# UART_Control.net
KiCad netlist of a schematic drawn in Altium Designer
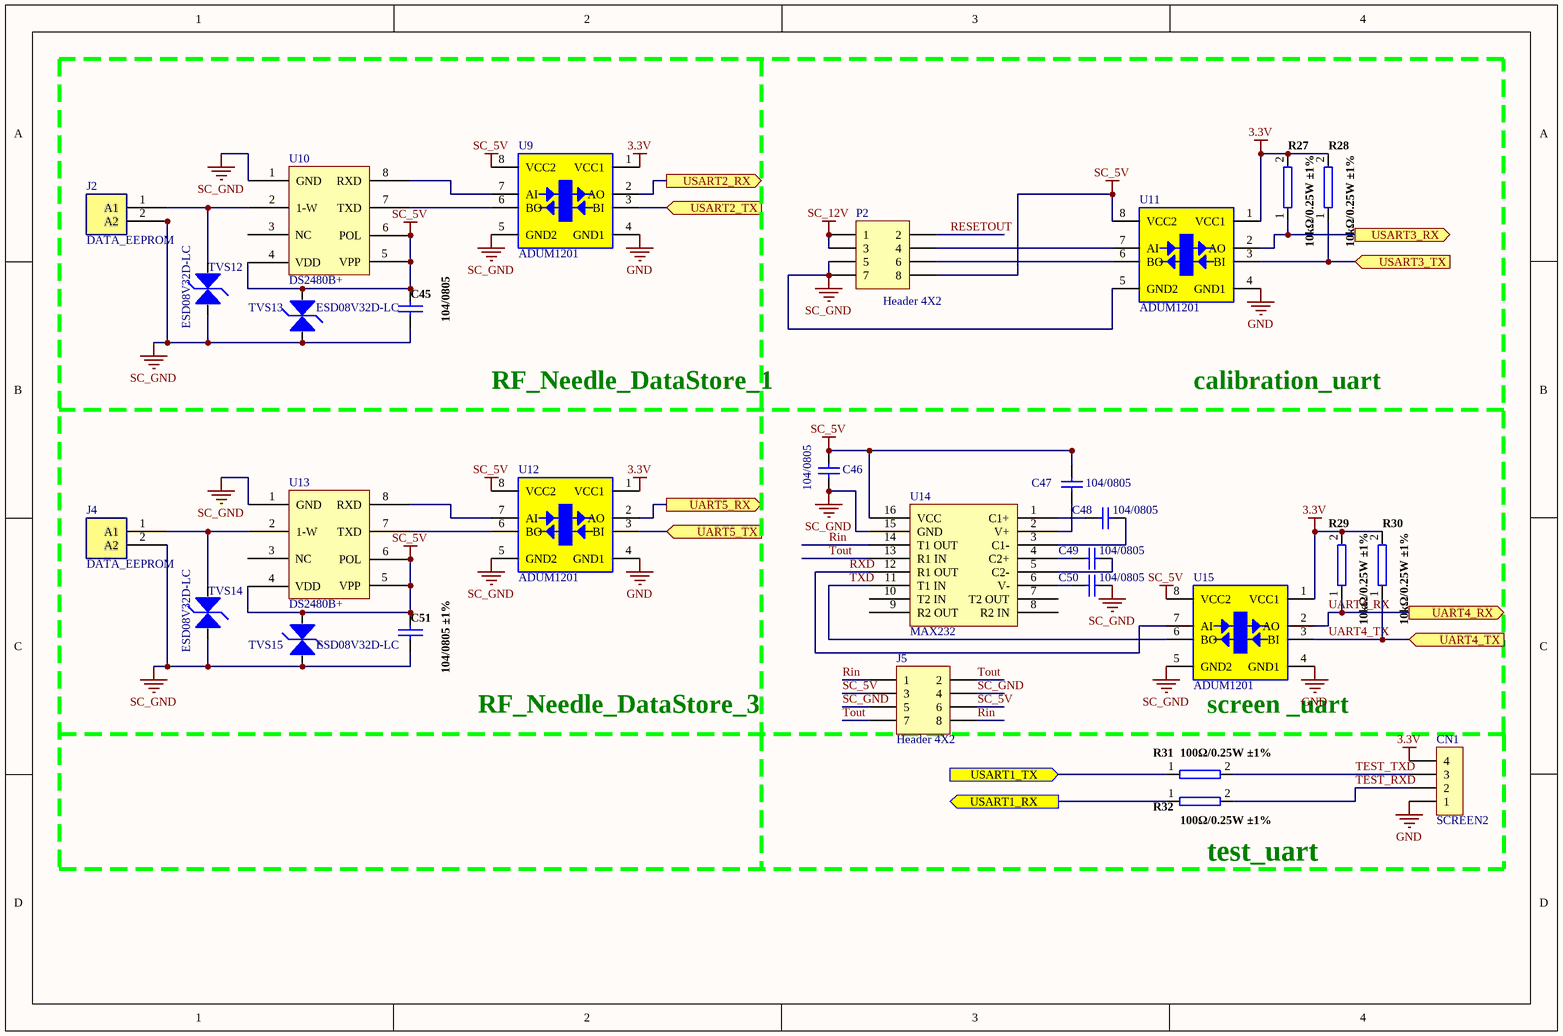
[diagram p0: UART_Control.SchDoc]

(export (version "E")
  (design (tool "Eeschema 10.0.6"))
  (components
    (comp (ref "C45")
      (value "104/0805")
      (footprint "C0805")
      (description "贴片电容 104/25V ±1% C0805")
      (libsource (lib "COOLCONTROL") (part "CAP"))
    )
    (comp (ref "C46")
      (value "104/0805")
      (footprint "C0805")
      (description "贴片电容 104/25V ±1% C0805")
      (fields (field (name "PUBLISHER") "Altium Limited"))
      (libsource (lib "Miscellaneous Devices") (part "Cap"))
    )
    (comp (ref "C47")
      (value "104/0805")
      (footprint "C0805")
      (description "贴片电容 104/25V ±1% C0805")
      (fields (field (name "PUBLISHER") "Altium Limited"))
      (libsource (lib "") (part "Cap_1"))
    )
    (comp (ref "C48")
      (value "104/0805")
      (footprint "C0805")
      (description "贴片电容 104/25V ±1% C0805")
      (fields (field (name "PUBLISHER") "Altium Limited"))
      (libsource (lib "") (part "Cap_1"))
    )
    (comp (ref "C49")
      (value "104/0805")
      (footprint "C0805")
      (description "贴片电容 104/25V ±1% C0805")
      (fields (field (name "PUBLISHER") "Altium Limited"))
      (libsource (lib "") (part "Cap_1"))
    )
    (comp (ref "C50")
      (value "104/0805")
      (footprint "C0805")
      (description "贴片电容 104/25V ±1% C0805")
      (fields (field (name "PUBLISHER") "Altium Limited"))
      (libsource (lib "") (part "Cap_1"))
    )
    (comp (ref "C51")
      (value "104/0805 ±1%")
      (footprint "C0805")
      (description "贴片电容 104/25V ±1% C0805")
      (libsource (lib "COOLCONTROL") (part "CAP"))
    )
    (comp (ref "CN1")
      (value "SCREEN2")
      (footprint "COOLCONTROL:4Pin-2.54")
      (description "单排排针（4针） 2.54mm 4Pin-2.54")
      (libsource (lib "COOLCONTROL") (part "CON4"))
    )
    (comp (ref "J2")
      (value "DATA_EEPROM")
      (footprint "COOLCONTROL:XH2")
      (description "插座式端子 XH2.54-2P 250V(DC/AC) 3A")
      (libsource (lib "COOLCONTROL") (part "CON2"))
    )
    (comp (ref "J4")
      (value "DATA_EEPROM")
      (footprint "XH2")
      (description "插座式端子 XH2.54-2P 250V(DC/AC) 3A")
      (libsource (lib "COOLCONTROL") (part "CON2"))
    )
    (comp (ref "J5")
      (value "Header 4X2")
      (footprint "IDC4*2")
      (description "双排排针（4针） 2.54mm IDC4*2")
      (fields (field (name "PUBLISHER") "Altium Limited"))
      (libsource (lib "Miscellaneous Connectors") (part "Header 4X2"))
    )
    (comp (ref "P2")
      (value "Header 4X2")
      (footprint "pcb2D3D库0903:RJ45")
      (description "RJ45插座 RJ45")
      (fields (field (name "PUBLISHER") "Altium Limited"))
      (libsource (lib "Miscellaneous Connectors") (part "Header 4X2"))
    )
    (comp (ref "R27")
      (value "10kΩ/0.25W ±1%")
      (footprint "R0805")
      (description "贴片电阻 10kΩ 0.25W ±1% R0805")
      (libsource (lib "*") (part "RES2"))
    )
    (comp (ref "R28")
      (value "10kΩ/0.25W ±1%")
      (footprint "R0805")
      (description "贴片电阻 10kΩ 0.25W ±1% R0805")
      (libsource (lib "*") (part "RES2"))
    )
    (comp (ref "R29")
      (value "10kΩ/0.25W ±1%")
      (footprint "R0805")
      (description "贴片电阻 10kΩ 0.25W ±1% R0805")
      (libsource (lib "*") (part "RES2"))
    )
    (comp (ref "R30")
      (value "10kΩ/0.25W ±1%")
      (footprint "R0805")
      (description "贴片电阻 10kΩ 0.25W ±1% R0805")
      (libsource (lib "*") (part "RES2"))
    )
    (comp (ref "R31")
      (value "100Ω/0.25W ±1%")
      (footprint "COOLCONTROL:R0805")
      (description "贴片电阻 100Ω 0.25W ±1% R0805")
      (libsource (lib "*") (part "RES2"))
    )
    (comp (ref "R32")
      (value "100Ω/0.25W ±1%")
      (footprint "COOLCONTROL:R0805")
      (description "贴片电阻 100Ω 0.25W ±1% R0805")
      (libsource (lib "*") (part "RES2"))
    )
    (comp (ref "TVS12")
      (value "ESD08V32D-LC")
      (footprint "SOD323")
      (description "ESD静电二极管 ESD08V32D-LC 5V 15KV 40A SOD323")
      (libsource (lib "COOLCONTROL") (part "TVS"))
    )
    (comp (ref "TVS13")
      (value "ESD08V32D-LC")
      (footprint "SOD323")
      (description "ESD静电二极管 ESD08V32D-LC 5V 15KV 40A SOD323")
      (libsource (lib "COOLCONTROL") (part "TVS"))
    )
    (comp (ref "TVS14")
      (value "ESD08V32D-LC")
      (footprint "SOD323")
      (description "ESD静电二极管 ESD08V32D-LC 5V 15KV 40A SOD323")
      (libsource (lib "COOLCONTROL") (part "TVS"))
    )
    (comp (ref "TVS15")
      (value "ESD08V32D-LC")
      (footprint "SOD323")
      (description "ESD静电二极管 ESD08V32D-LC 5V 15KV 40A SOD323")
      (libsource (lib "COOLCONTROL") (part "TVS"))
    )
    (comp (ref "U9")
      (value "ADUM1201")
      (footprint "SOIC8_N")
      (description "双通道数字隔离器 ADUM1201 SOIC8_N")
      (libsource (lib "COOLCONTROL") (part "ADUM1201"))
    )
    (comp (ref "U10")
      (value "DS2480B+")
      (footprint "SOIC8_N")
      (description "1-Wire线驱动器 DS2480B SOIC8_N")
      (libsource (lib "COOLCONTROL") (part "DS2480B+"))
    )
    (comp (ref "U11")
      (value "ADUM1201")
      (footprint "SOIC8_N")
      (description "双通道数字隔离器 ADUM1201 SOIC8_N")
      (libsource (lib "COOLCONTROL") (part "ADUM1201"))
    )
    (comp (ref "U12")
      (value "ADUM1201")
      (footprint "SOIC8_N")
      (description "双通道数字隔离器 ADUM1201 SOIC8_N")
      (libsource (lib "COOLCONTROL") (part "ADUM1201"))
    )
    (comp (ref "U13")
      (value "DS2480B+")
      (footprint "SOIC8_N")
      (description "1-Wire线驱动器 DS2480B SOIC8_N")
      (libsource (lib "COOLCONTROL") (part "DS2480B+"))
    )
    (comp (ref "U14")
      (value "MAX232")
      (footprint "SOP16")
      (description "串口通信转换芯片 MAX232 SOP16")
      (libsource (lib "miniCoreBoard") (part "MAX232_DIP16"))
    )
    (comp (ref "U15")
      (value "ADUM1201")
      (footprint "SOIC8_N")
      (description "双通道数字隔离器 ADUM1201 SOIC8_N")
      (libsource (lib "COOLCONTROL") (part "ADUM1201"))
    )
  )
  (nets
    (net (code "1") (name "/RESETOUT") (class "Default")
      (node (ref "P2") (pin "2") (pinfunction "2_2") (pintype "passive"))
    )
    (net (code "2") (name "/RXD") (class "Default")
      (node (ref "U14") (pin "12") (pinfunction "R1_OUT_12") (pintype "passive"))
      (node (ref "U15") (pin "7") (pinfunction "AI_7") (pintype "passive"))
    )
    (net (code "3") (name "/Rin") (class "Default")
      (node (ref "J5") (pin "1") (pinfunction "1_1") (pintype "passive"))
      (node (ref "J5") (pin "8") (pinfunction "8_8") (pintype "passive"))
      (node (ref "U14") (pin "14") (pinfunction "T1_OUT_14") (pintype "passive"))
    )
    (net (code "4") (name "/TEST_RXD") (class "Default")
      (node (ref "CN1") (pin "2") (pinfunction "2_2") (pintype "passive"))
      (node (ref "R32") (pin "2") (pintype "passive"))
    )
    (net (code "5") (name "/TEST_TXD") (class "Default")
      (node (ref "CN1") (pin "3") (pinfunction "3_3") (pintype "passive"))
      (node (ref "R31") (pin "2") (pintype "passive"))
    )
    (net (code "6") (name "/TXD") (class "Default")
      (node (ref "U14") (pin "11") (pinfunction "T1_IN_11") (pintype "passive"))
      (node (ref "U15") (pin "6") (pinfunction "BO_6") (pintype "passive"))
    )
    (net (code "7") (name "/Tout") (class "Default")
      (node (ref "J5") (pin "2") (pinfunction "2_2") (pintype "passive"))
      (node (ref "J5") (pin "7") (pinfunction "7_7") (pintype "passive"))
      (node (ref "U14") (pin "13") (pinfunction "R1_IN_13") (pintype "passive"))
    )
    (net (code "8") (name "/UART4_RX") (class "Default")
      (node (ref "R29") (pin "1") (pintype "passive"))
      (node (ref "U15") (pin "2") (pinfunction "AO_2") (pintype "passive"))
    )
    (net (code "9") (name "/UART4_TX") (class "Default")
      (node (ref "R30") (pin "1") (pintype "passive"))
      (node (ref "U15") (pin "3") (pinfunction "BI_3") (pintype "passive"))
    )
    (net (code "10") (name "/UART5_RX") (class "Default")
      (node (ref "U12") (pin "2") (pinfunction "AO_2") (pintype "passive"))
    )
    (net (code "11") (name "/UART5_TX") (class "Default")
      (node (ref "U12") (pin "3") (pinfunction "BI_3") (pintype "passive"))
    )
    (net (code "12") (name "/USART1_RX") (class "Default") (node (ref "R32") (pin "1") (pintype "passive")))
    (net (code "13") (name "/USART1_TX") (class "Default") (node (ref "R31") (pin "1") (pintype "passive")))
    (net (code "14") (name "/USART2_RX") (class "Default")
      (node (ref "U9") (pin "2") (pinfunction "AO_2") (pintype "passive"))
    )
    (net (code "15") (name "/USART2_TX") (class "Default")
      (node (ref "U9") (pin "3") (pinfunction "BI_3") (pintype "passive"))
    )
    (net (code "16") (name "/USART3_RX") (class "Default")
      (node (ref "R27") (pin "1") (pintype "passive"))
      (node (ref "U11") (pin "2") (pinfunction "AO_2") (pintype "passive"))
    )
    (net (code "17") (name "/USART3_TX") (class "Default")
      (node (ref "R28") (pin "1") (pintype "passive"))
      (node (ref "U11") (pin "3") (pinfunction "BI_3") (pintype "passive"))
    )
    (net (code "18") (name "3.3V") (class "Default")
      (node (ref "CN1") (pin "4") (pinfunction "4_4") (pintype "passive"))
      (node (ref "R27") (pin "2") (pintype "passive"))
      (node (ref "R28") (pin "2") (pintype "passive"))
      (node (ref "R29") (pin "2") (pintype "passive"))
      (node (ref "R30") (pin "2") (pintype "passive"))
      (node (ref "U11") (pin "1") (pinfunction "VCC1_1") (pintype "passive"))
      (node (ref "U12") (pin "1") (pinfunction "VCC1_1") (pintype "passive"))
      (node (ref "U15") (pin "1") (pinfunction "VCC1_1") (pintype "passive"))
      (node (ref "U9") (pin "1") (pinfunction "VCC1_1") (pintype "passive"))
    )
    (net (code "19") (name "GND") (class "Default")
      (node (ref "CN1") (pin "1") (pinfunction "1_1") (pintype "passive"))
      (node (ref "U11") (pin "4") (pinfunction "GND1_4") (pintype "passive"))
      (node (ref "U12") (pin "4") (pinfunction "GND1_4") (pintype "passive"))
      (node (ref "U15") (pin "4") (pinfunction "GND1_4") (pintype "passive"))
      (node (ref "U9") (pin "4") (pinfunction "GND1_4") (pintype "passive"))
    )
    (net (code "20") (name "Net-(J2-A1)") (class "Default")
      (node (ref "J2") (pin "1") (pinfunction "A1_1") (pintype "passive"))
      (node (ref "TVS12") (pin "1") (pinfunction "1_1") (pintype "passive"))
      (node (ref "U10") (pin "2") (pinfunction "1-W_2") (pintype "passive"))
    )
    (net (code "21") (name "Net-(J4-A1)") (class "Default")
      (node (ref "J4") (pin "1") (pinfunction "A1_1") (pintype "passive"))
      (node (ref "TVS14") (pin "1") (pinfunction "1_1") (pintype "passive"))
      (node (ref "U13") (pin "2") (pinfunction "1-W_2") (pintype "passive"))
    )
    (net (code "22") (name "Net-(U10-RXD)") (class "Default")
      (node (ref "U10") (pin "8") (pinfunction "RXD_8") (pintype "passive"))
      (node (ref "U9") (pin "7") (pinfunction "AI_7") (pintype "passive"))
    )
    (net (code "23") (name "Net-(U10-TXD)") (class "Default")
      (node (ref "U10") (pin "7") (pinfunction "TXD_7") (pintype "passive"))
      (node (ref "U9") (pin "6") (pinfunction "BO_6") (pintype "passive"))
    )
    (net (code "24") (name "Net-(U11-AI)") (class "Default")
      (node (ref "P2") (pin "4") (pinfunction "4_4") (pintype "passive"))
      (node (ref "U11") (pin "7") (pinfunction "AI_7") (pintype "passive"))
    )
    (net (code "25") (name "Net-(U11-BO)") (class "Default")
      (node (ref "P2") (pin "6") (pinfunction "6_6") (pintype "passive"))
      (node (ref "U11") (pin "6") (pinfunction "BO_6") (pintype "passive"))
    )
    (net (code "26") (name "Net-(U12-AI)") (class "Default")
      (node (ref "U12") (pin "7") (pinfunction "AI_7") (pintype "passive"))
      (node (ref "U13") (pin "8") (pinfunction "RXD_8") (pintype "passive"))
    )
    (net (code "27") (name "Net-(U12-BO)") (class "Default")
      (node (ref "U12") (pin "6") (pinfunction "BO_6") (pintype "passive"))
      (node (ref "U13") (pin "7") (pinfunction "TXD_7") (pintype "passive"))
    )
    (net (code "28") (name "Net-(U14-C1+)") (class "Default")
      (node (ref "C48") (pin "1") (pinfunction "1_1") (pintype "passive"))
      (node (ref "U14") (pin "1") (pinfunction "C1+_1") (pintype "passive"))
    )
    (net (code "29") (name "Net-(U14-C1-)") (class "Default")
      (node (ref "C48") (pin "2") (pinfunction "2_2") (pintype "passive"))
      (node (ref "U14") (pin "3") (pinfunction "C1-_3") (pintype "passive"))
    )
    (net (code "30") (name "Net-(U14-C2+)") (class "Default")
      (node (ref "C49") (pin "1") (pinfunction "1_1") (pintype "passive"))
      (node (ref "U14") (pin "4") (pinfunction "C2+_4") (pintype "passive"))
    )
    (net (code "31") (name "Net-(U14-C2-)") (class "Default")
      (node (ref "C49") (pin "2") (pinfunction "2_2") (pintype "passive"))
      (node (ref "U14") (pin "5") (pinfunction "C2-_5") (pintype "passive"))
    )
    (net (code "32") (name "Net-(U14-V+)") (class "Default")
      (node (ref "C47") (pin "2") (pinfunction "2_2") (pintype "passive"))
      (node (ref "U14") (pin "2") (pinfunction "V+_2") (pintype "passive"))
    )
    (net (code "33") (name "Net-(U14-V-)") (class "Default")
      (node (ref "C50") (pin "1") (pinfunction "1_1") (pintype "passive"))
      (node (ref "U14") (pin "6") (pinfunction "V-_6") (pintype "passive"))
    )
    (net (code "34") (name "SC_5V") (class "Default")
      (node (ref "C45") (pin "2") (pinfunction "2_2") (pintype "passive"))
      (node (ref "C46") (pin "2") (pinfunction "2_2") (pintype "passive"))
      (node (ref "C47") (pin "1") (pinfunction "1_1") (pintype "passive"))
      (node (ref "C51") (pin "2") (pinfunction "2_2") (pintype "passive"))
      (node (ref "J5") (pin "3") (pinfunction "3_3") (pintype "passive"))
      (node (ref "J5") (pin "6") (pinfunction "6_6") (pintype "passive"))
      (node (ref "P2") (pin "8") (pinfunction "8_8") (pintype "passive"))
      (node (ref "TVS13") (pin "1") (pinfunction "1_1") (pintype "passive"))
      (node (ref "TVS15") (pin "1") (pinfunction "1_1") (pintype "passive"))
      (node (ref "U10") (pin "4") (pinfunction "VDD_4") (pintype "passive"))
      (node (ref "U10") (pin "5") (pinfunction "VPP_5") (pintype "passive"))
      (node (ref "U10") (pin "6") (pinfunction "POL_6") (pintype "passive"))
      (node (ref "U11") (pin "8") (pinfunction "VCC2_8") (pintype "passive"))
      (node (ref "U12") (pin "8") (pinfunction "VCC2_8") (pintype "passive"))
      (node (ref "U13") (pin "4") (pinfunction "VDD_4") (pintype "passive"))
      (node (ref "U13") (pin "5") (pinfunction "VPP_5") (pintype "passive"))
      (node (ref "U13") (pin "6") (pinfunction "POL_6") (pintype "passive"))
      (node (ref "U14") (pin "16") (pinfunction "VCC_16") (pintype "passive"))
      (node (ref "U15") (pin "8") (pinfunction "VCC2_8") (pintype "passive"))
      (node (ref "U9") (pin "8") (pinfunction "VCC2_8") (pintype "passive"))
    )
    (net (code "35") (name "SC_12V") (class "Default")
      (node (ref "P2") (pin "1") (pinfunction "1_1") (pintype "passive"))
      (node (ref "P2") (pin "3") (pinfunction "3_3") (pintype "passive"))
    )
    (net (code "36") (name "SC_GND") (class "Default")
      (node (ref "C45") (pin "1") (pinfunction "1_1") (pintype "passive"))
      (node (ref "C46") (pin "1") (pinfunction "1_1") (pintype "passive"))
      (node (ref "C50") (pin "2") (pinfunction "2_2") (pintype "passive"))
      (node (ref "C51") (pin "1") (pinfunction "1_1") (pintype "passive"))
      (node (ref "J2") (pin "2") (pinfunction "A2_2") (pintype "passive"))
      (node (ref "J4") (pin "2") (pinfunction "A2_2") (pintype "passive"))
      (node (ref "J5") (pin "4") (pinfunction "4_4") (pintype "passive"))
      (node (ref "J5") (pin "5") (pinfunction "5_5") (pintype "passive"))
      (node (ref "P2") (pin "5") (pinfunction "5_5") (pintype "passive"))
      (node (ref "P2") (pin "7") (pinfunction "7_7") (pintype "passive"))
      (node (ref "TVS12") (pin "2") (pinfunction "2_2") (pintype "passive"))
      (node (ref "TVS13") (pin "2") (pinfunction "2_2") (pintype "passive"))
      (node (ref "TVS14") (pin "2") (pinfunction "2_2") (pintype "passive"))
      (node (ref "TVS15") (pin "2") (pinfunction "2_2") (pintype "passive"))
      (node (ref "U10") (pin "1") (pinfunction "GND_1") (pintype "passive"))
      (node (ref "U11") (pin "5") (pinfunction "GND2_5") (pintype "passive"))
      (node (ref "U12") (pin "5") (pinfunction "GND2_5") (pintype "passive"))
      (node (ref "U13") (pin "1") (pinfunction "GND_1") (pintype "passive"))
      (node (ref "U14") (pin "15") (pinfunction "GND_15") (pintype "passive"))
      (node (ref "U15") (pin "5") (pinfunction "GND2_5") (pintype "passive"))
      (node (ref "U9") (pin "5") (pinfunction "GND2_5") (pintype "passive"))
    )
    (net (code "37") (name "unconnected-(U10-NC-Pad3)") (class "Default")
      (node (ref "U10") (pin "3") (pinfunction "NC_3") (pintype "passive"))
    )
    (net (code "38") (name "unconnected-(U13-NC-Pad3)") (class "Default")
      (node (ref "U13") (pin "3") (pinfunction "NC_3") (pintype "passive"))
    )
    (net (code "39") (name "unconnected-(U14-R2_IN-Pad8)") (class "Default")
      (node (ref "U14") (pin "8") (pinfunction "R2_IN_8") (pintype "passive"))
    )
    (net (code "40") (name "unconnected-(U14-R2_OUT-Pad9)") (class "Default")
      (node (ref "U14") (pin "9") (pinfunction "R2_OUT_9") (pintype "passive"))
    )
    (net (code "41") (name "unconnected-(U14-T2_IN-Pad10)") (class "Default")
      (node (ref "U14") (pin "10") (pinfunction "T2_IN_10") (pintype "passive"))
    )
    (net (code "42") (name "unconnected-(U14-T2_OUT-Pad7)") (class "Default")
      (node (ref "U14") (pin "7") (pinfunction "T2_OUT_7") (pintype "passive"))
    )
  )
)
